# Cube_Schematic.net
KiCad netlist of a schematic drawn in EAGLE
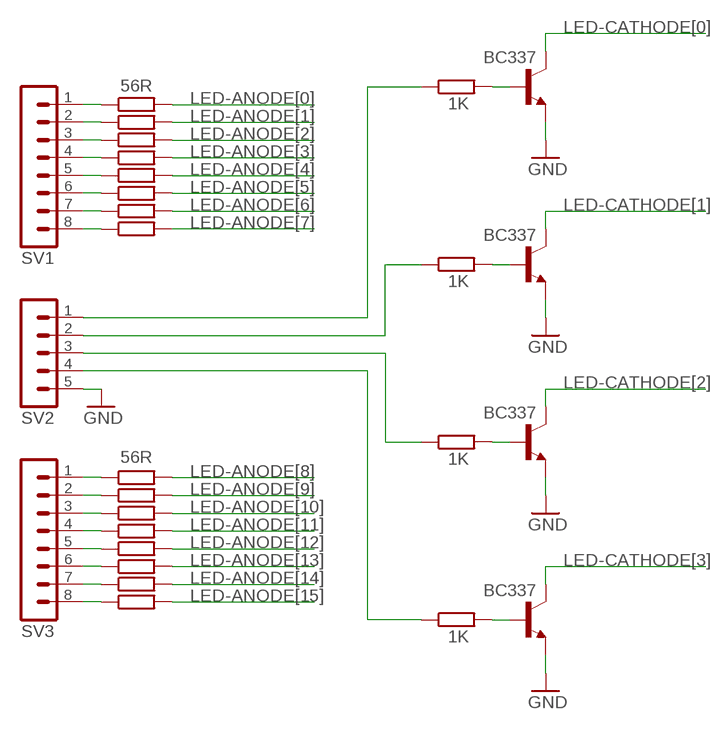
[diagram p0: schematic, sheet 1]

(export (version "E")
  (design (tool "Eeschema 10.0.6"))
  (components
    (comp (ref "R1")
      (value "56R")
      (footprint "eagle-import:0204_7")
      (libsource (lib "eagle-import") (part "resistor_R-EU_0204/7"))
    )
    (comp (ref "R2")
      (value "56R")
      (footprint "eagle-import:0204_7")
      (libsource (lib "eagle-import") (part "resistor_R-EU_0204/7"))
    )
    (comp (ref "R3")
      (value "56R")
      (footprint "eagle-import:0204_7")
      (libsource (lib "eagle-import") (part "resistor_R-EU_0204/7"))
    )
    (comp (ref "R4")
      (value "56R")
      (footprint "eagle-import:0204_7")
      (libsource (lib "eagle-import") (part "resistor_R-EU_0204/7"))
    )
    (comp (ref "R5")
      (value "56R")
      (footprint "eagle-import:0204_7")
      (libsource (lib "eagle-import") (part "resistor_R-EU_0204/7"))
    )
    (comp (ref "R6")
      (value "56R")
      (footprint "eagle-import:0204_7")
      (libsource (lib "eagle-import") (part "resistor_R-EU_0204/7"))
    )
    (comp (ref "R7")
      (value "56R")
      (footprint "eagle-import:0204_7")
      (libsource (lib "eagle-import") (part "resistor_R-EU_0204/7"))
    )
    (comp (ref "R8")
      (value "56R")
      (footprint "eagle-import:0204_7")
      (libsource (lib "eagle-import") (part "resistor_R-EU_0204/7"))
    )
    (comp (ref "R9")
      (value "56R")
      (footprint "eagle-import:0204_7")
      (libsource (lib "eagle-import") (part "resistor_R-EU_0204/7"))
    )
    (comp (ref "R10")
      (value "56R")
      (footprint "eagle-import:0204_7")
      (libsource (lib "eagle-import") (part "resistor_R-EU_0204/7"))
    )
    (comp (ref "R11")
      (value "56R")
      (footprint "eagle-import:0204_7")
      (libsource (lib "eagle-import") (part "resistor_R-EU_0204/7"))
    )
    (comp (ref "R12")
      (value "56R")
      (footprint "eagle-import:0204_7")
      (libsource (lib "eagle-import") (part "resistor_R-EU_0204/7"))
    )
    (comp (ref "R13")
      (value "56R")
      (footprint "eagle-import:0204_7")
      (libsource (lib "eagle-import") (part "resistor_R-EU_0204/7"))
    )
    (comp (ref "R14")
      (value "56R")
      (footprint "eagle-import:0204_7")
      (libsource (lib "eagle-import") (part "resistor_R-EU_0204/7"))
    )
    (comp (ref "R15")
      (value "56R")
      (footprint "eagle-import:0204_7")
      (libsource (lib "eagle-import") (part "resistor_R-EU_0204/7"))
    )
    (comp (ref "R16")
      (value "56R")
      (footprint "eagle-import:0204_7")
      (libsource (lib "eagle-import") (part "resistor_R-EU_0204/7"))
    )
    (comp (ref "R17")
      (value "1K")
      (footprint "eagle-import:0204_7")
      (libsource (lib "eagle-import") (part "R-EU_0204/7"))
    )
    (comp (ref "R18")
      (value "1K")
      (footprint "eagle-import:0204_7")
      (libsource (lib "eagle-import") (part "R-EU_0204/7"))
    )
    (comp (ref "R19")
      (value "1K")
      (footprint "eagle-import:0204_7")
      (libsource (lib "eagle-import") (part "R-EU_0204/7"))
    )
    (comp (ref "R20")
      (value "1K")
      (footprint "eagle-import:0204_7")
      (libsource (lib "eagle-import") (part "R-EU_0204/7"))
    )
    (comp (ref "SV1")
      (value "MA08-1")
      (footprint "eagle-import:MA08-1")
      (libsource (lib "eagle-import") (part "MA08-1"))
    )
    (comp (ref "SV2")
      (value "MA05-1")
      (footprint "eagle-import:MA05-1")
      (libsource (lib "eagle-import") (part "MA05-1"))
    )
    (comp (ref "SV3")
      (value "MA08-1")
      (footprint "eagle-import:MA08-1")
      (libsource (lib "eagle-import") (part "MA08-1"))
    )
    (comp (ref "T1")
      (value "BC337")
      (footprint "eagle-import:TO92")
      (libsource (lib "eagle-import") (part "BC337"))
    )
    (comp (ref "T2")
      (value "BC337")
      (footprint "eagle-import:TO92")
      (libsource (lib "eagle-import") (part "BC337"))
    )
    (comp (ref "T3")
      (value "BC337")
      (footprint "eagle-import:TO92")
      (libsource (lib "eagle-import") (part "BC337"))
    )
    (comp (ref "T4")
      (value "BC337")
      (footprint "eagle-import:TO92")
      (libsource (lib "eagle-import") (part "BC337"))
    )
  )
  (nets
    (net (code "1") (name "/LED-ANODE[0]") (class "Default")
      (node (ref "R1") (pin "2") (pinfunction "2_2") (pintype "passive"))
    )
    (net (code "2") (name "/LED-ANODE[1]") (class "Default")
      (node (ref "R2") (pin "2") (pinfunction "2_2") (pintype "passive"))
    )
    (net (code "3") (name "/LED-ANODE[2]") (class "Default")
      (node (ref "R3") (pin "2") (pinfunction "2_2") (pintype "passive"))
    )
    (net (code "4") (name "/LED-ANODE[3]") (class "Default")
      (node (ref "R4") (pin "2") (pinfunction "2_2") (pintype "passive"))
    )
    (net (code "5") (name "/LED-ANODE[4]") (class "Default")
      (node (ref "R5") (pin "2") (pinfunction "2_2") (pintype "passive"))
    )
    (net (code "6") (name "/LED-ANODE[5]") (class "Default")
      (node (ref "R6") (pin "2") (pinfunction "2_2") (pintype "passive"))
    )
    (net (code "7") (name "/LED-ANODE[6]") (class "Default")
      (node (ref "R7") (pin "2") (pinfunction "2_2") (pintype "passive"))
    )
    (net (code "8") (name "/LED-ANODE[7]") (class "Default")
      (node (ref "R8") (pin "2") (pinfunction "2_2") (pintype "passive"))
    )
    (net (code "9") (name "/LED-ANODE[8]") (class "Default")
      (node (ref "R9") (pin "2") (pinfunction "2_2") (pintype "passive"))
    )
    (net (code "10") (name "/LED-ANODE[9]") (class "Default")
      (node (ref "R10") (pin "2") (pinfunction "2_2") (pintype "passive"))
    )
    (net (code "11") (name "/LED-ANODE[10]") (class "Default")
      (node (ref "R11") (pin "2") (pinfunction "2_2") (pintype "passive"))
    )
    (net (code "12") (name "/LED-ANODE[11]") (class "Default")
      (node (ref "R12") (pin "2") (pinfunction "2_2") (pintype "passive"))
    )
    (net (code "13") (name "/LED-ANODE[12]") (class "Default")
      (node (ref "R13") (pin "2") (pinfunction "2_2") (pintype "passive"))
    )
    (net (code "14") (name "/LED-ANODE[13]") (class "Default")
      (node (ref "R14") (pin "2") (pinfunction "2_2") (pintype "passive"))
    )
    (net (code "15") (name "/LED-ANODE[14]") (class "Default")
      (node (ref "R15") (pin "2") (pinfunction "2_2") (pintype "passive"))
    )
    (net (code "16") (name "/LED-ANODE[15]") (class "Default")
      (node (ref "R16") (pin "2") (pinfunction "2_2") (pintype "passive"))
    )
    (net (code "17") (name "/LED-CATHODE[0]") (class "Default")
      (node (ref "T1") (pin "3") (pinfunction "C_3") (pintype "passive"))
    )
    (net (code "18") (name "/LED-CATHODE[1]") (class "Default")
      (node (ref "T2") (pin "3") (pinfunction "C_3") (pintype "passive"))
    )
    (net (code "19") (name "/LED-CATHODE[2]") (class "Default")
      (node (ref "T3") (pin "3") (pinfunction "C_3") (pintype "passive"))
    )
    (net (code "20") (name "/LED-CATHODE[3]") (class "Default")
      (node (ref "T4") (pin "3") (pinfunction "C_3") (pintype "passive"))
    )
    (net (code "21") (name "GND") (class "Default")
      (node (ref "SV2") (pin "5") (pinfunction "5_5") (pintype "passive"))
      (node (ref "T1") (pin "1") (pinfunction "E_1") (pintype "passive"))
      (node (ref "T2") (pin "1") (pinfunction "E_1") (pintype "passive"))
      (node (ref "T3") (pin "1") (pinfunction "E_1") (pintype "passive"))
      (node (ref "T4") (pin "1") (pinfunction "E_1") (pintype "passive"))
    )
    (net (code "22") (name "Net-(R1-Pad1)") (class "Default")
      (node (ref "R1") (pin "1") (pinfunction "1_1") (pintype "passive"))
      (node (ref "SV1") (pin "1") (pinfunction "1_1") (pintype "passive"))
    )
    (net (code "23") (name "Net-(R2-Pad1)") (class "Default")
      (node (ref "R2") (pin "1") (pinfunction "1_1") (pintype "passive"))
      (node (ref "SV1") (pin "2") (pinfunction "2_2") (pintype "passive"))
    )
    (net (code "24") (name "Net-(R3-Pad1)") (class "Default")
      (node (ref "R3") (pin "1") (pinfunction "1_1") (pintype "passive"))
      (node (ref "SV1") (pin "3") (pinfunction "3_3") (pintype "passive"))
    )
    (net (code "25") (name "Net-(R4-Pad1)") (class "Default")
      (node (ref "R4") (pin "1") (pinfunction "1_1") (pintype "passive"))
      (node (ref "SV1") (pin "4") (pinfunction "4_4") (pintype "passive"))
    )
    (net (code "26") (name "Net-(R5-Pad1)") (class "Default")
      (node (ref "R5") (pin "1") (pinfunction "1_1") (pintype "passive"))
      (node (ref "SV1") (pin "5") (pinfunction "5_5") (pintype "passive"))
    )
    (net (code "27") (name "Net-(R6-Pad1)") (class "Default")
      (node (ref "R6") (pin "1") (pinfunction "1_1") (pintype "passive"))
      (node (ref "SV1") (pin "6") (pinfunction "6_6") (pintype "passive"))
    )
    (net (code "28") (name "Net-(R7-Pad1)") (class "Default")
      (node (ref "R7") (pin "1") (pinfunction "1_1") (pintype "passive"))
      (node (ref "SV1") (pin "7") (pinfunction "7_7") (pintype "passive"))
    )
    (net (code "29") (name "Net-(R8-Pad1)") (class "Default")
      (node (ref "R8") (pin "1") (pinfunction "1_1") (pintype "passive"))
      (node (ref "SV1") (pin "8") (pinfunction "8_8") (pintype "passive"))
    )
    (net (code "30") (name "Net-(R9-Pad1)") (class "Default")
      (node (ref "R9") (pin "1") (pinfunction "1_1") (pintype "passive"))
      (node (ref "SV3") (pin "1") (pinfunction "1_1") (pintype "passive"))
    )
    (net (code "31") (name "Net-(R10-Pad1)") (class "Default")
      (node (ref "R10") (pin "1") (pinfunction "1_1") (pintype "passive"))
      (node (ref "SV3") (pin "2") (pinfunction "2_2") (pintype "passive"))
    )
    (net (code "32") (name "Net-(R11-Pad1)") (class "Default")
      (node (ref "R11") (pin "1") (pinfunction "1_1") (pintype "passive"))
      (node (ref "SV3") (pin "3") (pinfunction "3_3") (pintype "passive"))
    )
    (net (code "33") (name "Net-(R12-Pad1)") (class "Default")
      (node (ref "R12") (pin "1") (pinfunction "1_1") (pintype "passive"))
      (node (ref "SV3") (pin "4") (pinfunction "4_4") (pintype "passive"))
    )
    (net (code "34") (name "Net-(R13-Pad1)") (class "Default")
      (node (ref "R13") (pin "1") (pinfunction "1_1") (pintype "passive"))
      (node (ref "SV3") (pin "5") (pinfunction "5_5") (pintype "passive"))
    )
    (net (code "35") (name "Net-(R14-Pad1)") (class "Default")
      (node (ref "R14") (pin "1") (pinfunction "1_1") (pintype "passive"))
      (node (ref "SV3") (pin "6") (pinfunction "6_6") (pintype "passive"))
    )
    (net (code "36") (name "Net-(R15-Pad1)") (class "Default")
      (node (ref "R15") (pin "1") (pinfunction "1_1") (pintype "passive"))
      (node (ref "SV3") (pin "7") (pinfunction "7_7") (pintype "passive"))
    )
    (net (code "37") (name "Net-(R16-Pad1)") (class "Default")
      (node (ref "R16") (pin "1") (pinfunction "1_1") (pintype "passive"))
      (node (ref "SV3") (pin "8") (pinfunction "8_8") (pintype "passive"))
    )
    (net (code "38") (name "Net-(R17-Pad1)") (class "Default")
      (node (ref "R17") (pin "1") (pinfunction "1_1") (pintype "passive"))
      (node (ref "SV2") (pin "1") (pinfunction "1_1") (pintype "passive"))
    )
    (net (code "39") (name "Net-(R18-Pad1)") (class "Default")
      (node (ref "R18") (pin "1") (pinfunction "1_1") (pintype "passive"))
      (node (ref "SV2") (pin "2") (pinfunction "2_2") (pintype "passive"))
    )
    (net (code "40") (name "Net-(R19-Pad1)") (class "Default")
      (node (ref "R19") (pin "1") (pinfunction "1_1") (pintype "passive"))
      (node (ref "SV2") (pin "3") (pinfunction "3_3") (pintype "passive"))
    )
    (net (code "41") (name "Net-(R20-Pad1)") (class "Default")
      (node (ref "R20") (pin "1") (pinfunction "1_1") (pintype "passive"))
      (node (ref "SV2") (pin "4") (pinfunction "4_4") (pintype "passive"))
    )
    (net (code "42") (name "Net-(T1-B)") (class "Default")
      (node (ref "R17") (pin "2") (pinfunction "2_2") (pintype "passive"))
      (node (ref "T1") (pin "2") (pinfunction "B_2") (pintype "passive"))
    )
    (net (code "43") (name "Net-(T2-B)") (class "Default")
      (node (ref "R18") (pin "2") (pinfunction "2_2") (pintype "passive"))
      (node (ref "T2") (pin "2") (pinfunction "B_2") (pintype "passive"))
    )
    (net (code "44") (name "Net-(T3-B)") (class "Default")
      (node (ref "R19") (pin "2") (pinfunction "2_2") (pintype "passive"))
      (node (ref "T3") (pin "2") (pinfunction "B_2") (pintype "passive"))
    )
    (net (code "45") (name "Net-(T4-B)") (class "Default")
      (node (ref "R20") (pin "2") (pinfunction "2_2") (pintype "passive"))
      (node (ref "T4") (pin "2") (pinfunction "B_2") (pintype "passive"))
    )
  )
)
